# MKRZero_V5_0.net
KiCad netlist of a schematic drawn in EAGLE
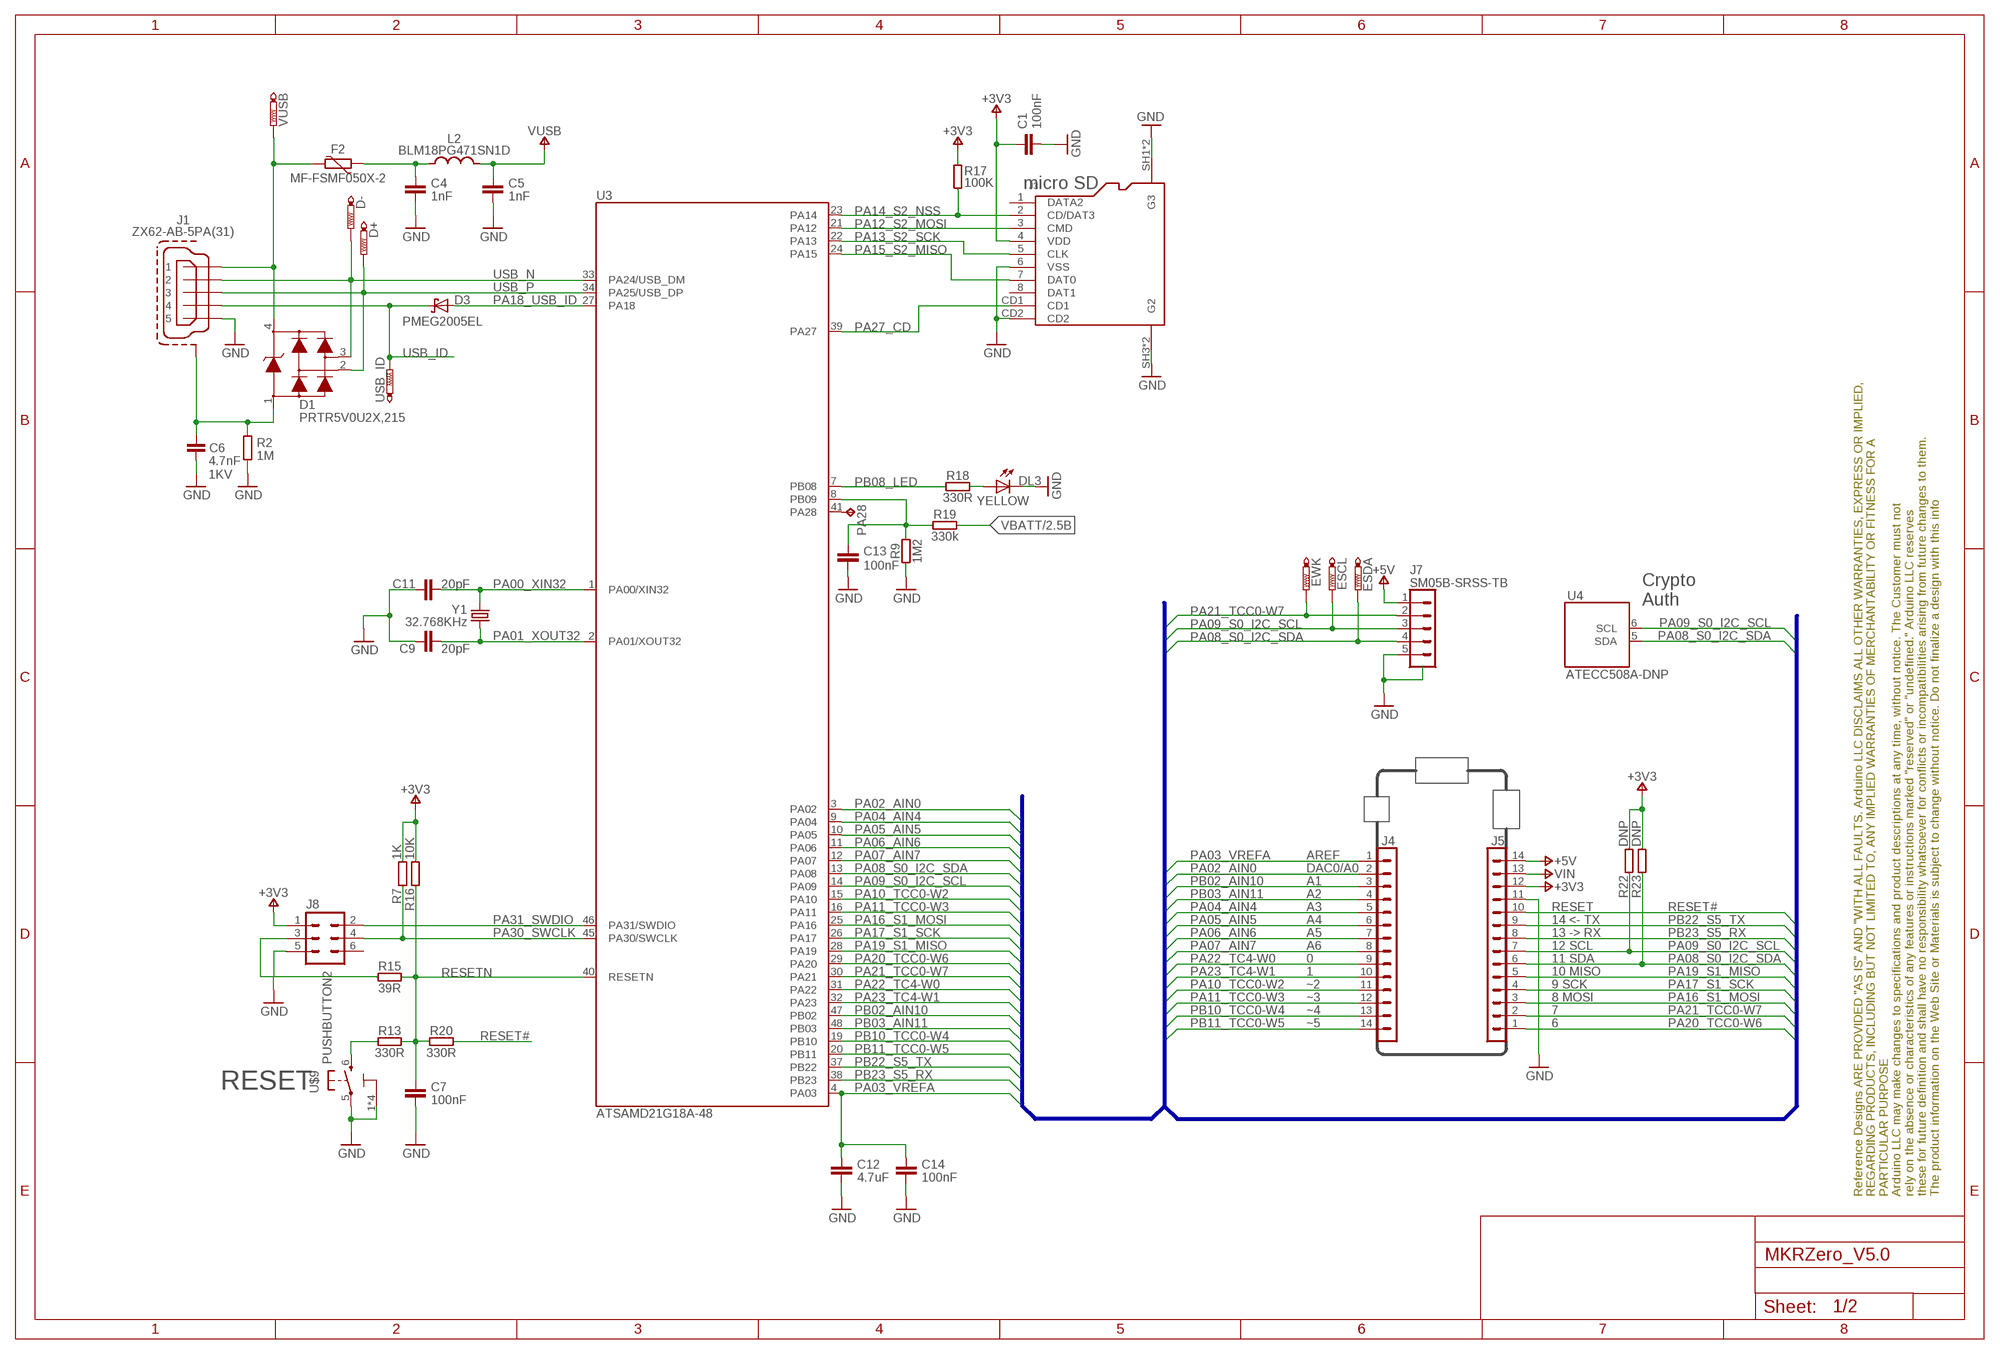
[diagram p0: schematic, sheet 1]
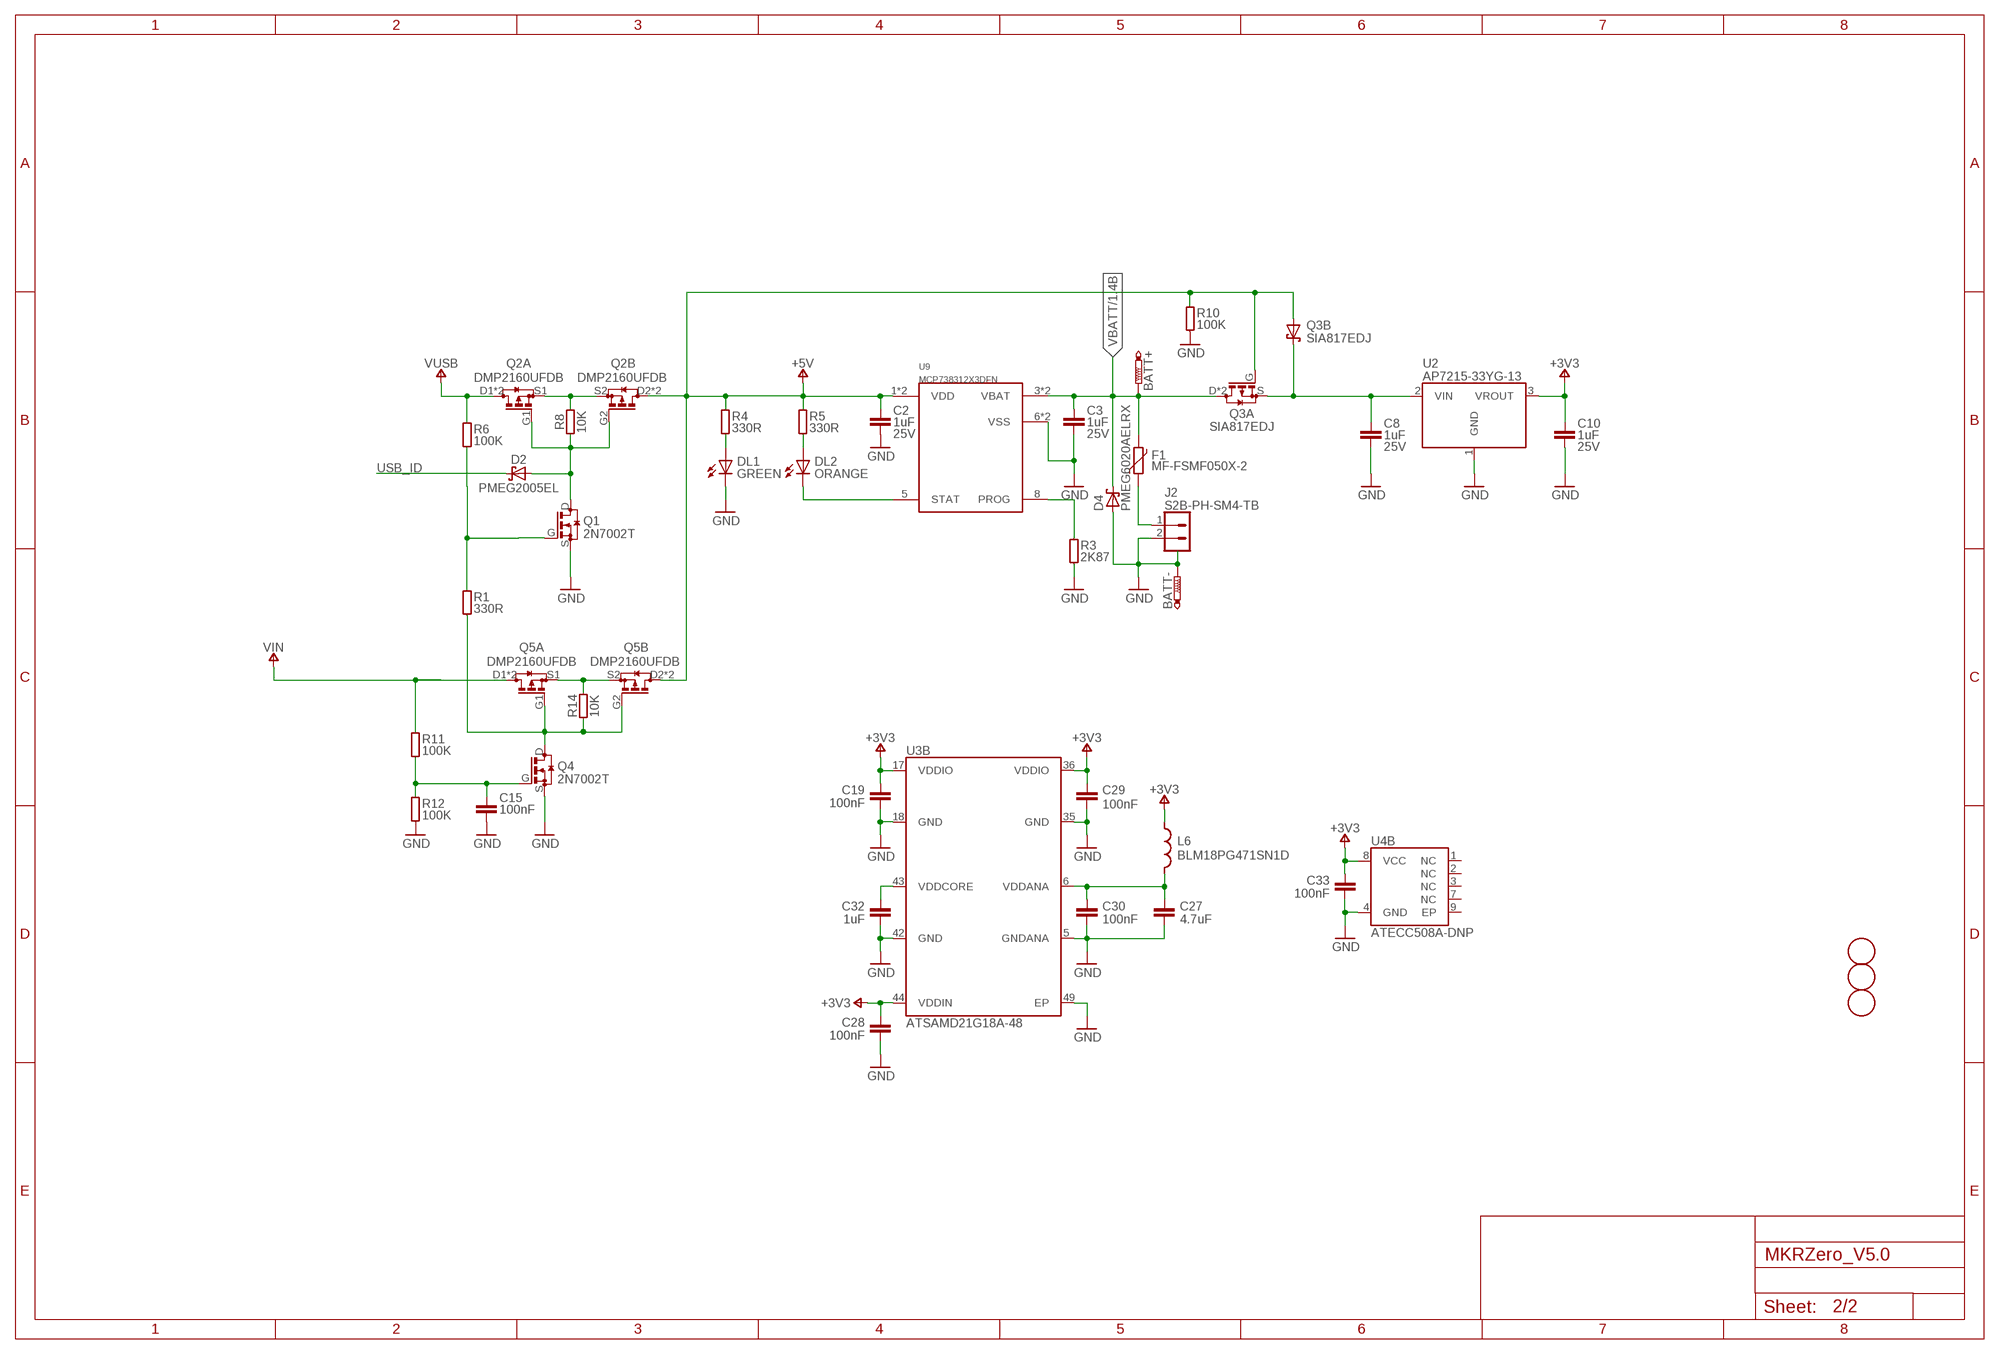
[diagram p1: schematic, sheet 2]

(export (version "E")
  (design (tool "Eeschema 10.0.6"))
  (components
    (comp (ref "BATT+")
      (value "PTR1B1,27")
      (footprint "eagle-import:B1,27")
      (libsource (lib "eagle-import") (part "PTR1B1,27"))
    )
    (comp (ref "BATT-")
      (value "PTR1B1,27")
      (footprint "eagle-import:B1,27")
      (libsource (lib "eagle-import") (part "PTR1B1,27"))
    )
    (comp (ref "C2")
      (value "1uF")
      (footprint "eagle-import:0402-1005X55N")
      (fields
        (field (name "MF") "Murata")
        (field (name "MPN") "GRM155R61E105KA12D ")
        (field (name "VOLTAGE") "25V")
      )
      (libsource (lib "eagle-import") (part "C-0402-1UF"))
    )
    (comp (ref "C3")
      (value "1uF")
      (footprint "eagle-import:0402-1005X55N")
      (fields
        (field (name "MF") "Murata")
        (field (name "MPN") "GRM155R61E105KA12D ")
        (field (name "VOLTAGE") "25V")
      )
      (libsource (lib "eagle-import") (part "C-0402-1UF"))
    )
    (comp (ref "C8")
      (value "1uF")
      (footprint "eagle-import:0402-1005X55N")
      (fields
        (field (name "MF") "Murata")
        (field (name "MPN") "GRM155R61E105KA12D ")
        (field (name "VOLTAGE") "25V")
      )
      (libsource (lib "eagle-import") (part "C-0402-1UF"))
    )
    (comp (ref "C10")
      (value "1uF")
      (footprint "eagle-import:0402-1005X55N")
      (fields
        (field (name "MF") "Murata")
        (field (name "MPN") "GRM155R61E105KA12D ")
        (field (name "VOLTAGE") "25V")
      )
      (libsource (lib "eagle-import") (part "C-0402-1UF"))
    )
    (comp (ref "C15")
      (value "100nF")
      (footprint "eagle-import:0402-1005X55N")
      (fields
        (field (name "MF") "Murata")
        (field (name "MPN") "GRM155R61E105KA12D ")
        (field (name "VOLTAGE") "25V")
      )
      (libsource (lib "eagle-import") (part "C-0402-1UF"))
    )
    (comp (ref "C19")
      (value "100nF")
      (footprint "eagle-import:0402-1005X55N")
      (fields (field (name "MF") "TDK") (field (name "MPN") "C1005X5R1H104K050BB "))
      (libsource (lib "eagle-import") (part "C-0402-100NF"))
    )
    (comp (ref "C27")
      (value "4.7uF")
      (footprint "eagle-import:0402-1005X55N")
      (fields (field (name "MF") "Murata") (field (name "MPN") "GRM155R60J475ME47D "))
      (libsource (lib "eagle-import") (part "C-0402-4.7UF"))
    )
    (comp (ref "C28")
      (value "100nF")
      (footprint "eagle-import:0402-1005X55N")
      (fields (field (name "MF") "TDK") (field (name "MPN") "C1005X5R1H104K050BB "))
      (libsource (lib "eagle-import") (part "C-0402-100NF"))
    )
    (comp (ref "C29")
      (value "100nF")
      (footprint "eagle-import:0402-1005X55N")
      (fields (field (name "MF") "TDK") (field (name "MPN") "C1005X5R1H104K050BB "))
      (libsource (lib "eagle-import") (part "C-0402-100NF"))
    )
    (comp (ref "C30")
      (value "100nF")
      (footprint "eagle-import:0402-1005X55N")
      (fields (field (name "MF") "TDK") (field (name "MPN") "C1005X5R1H104K050BB "))
      (libsource (lib "eagle-import") (part "C-0402-100NF"))
    )
    (comp (ref "C32")
      (value "1uF")
      (footprint "eagle-import:0402-1005X55N")
      (fields (field (name "MF") "Murata") (field (name "MPN") "GRM155R61E105KA12D "))
      (libsource (lib "eagle-import") (part "C-0402-1UF"))
    )
    (comp (ref "C33")
      (value "100nF")
      (footprint "eagle-import:0402-1005X55N")
      (fields (field (name "MF") "TDK") (field (name "MPN") "C1005X5R1H104K050BB "))
      (libsource (lib "eagle-import") (part "C-0402-100NF"))
    )
    (comp (ref "D2")
      (value "PMEG2005EL")
      (footprint "eagle-import:SODFL1008X40N-882D")
      (fields (field (name "MF") "NXP") (field (name "MPN") "PMEG2005EL,315 "))
      (libsource (lib "eagle-import") (part "PMEG2005EL"))
    )
    (comp (ref "D4")
      (value "PMEG6020AELRX")
      (footprint "eagle-import:SMA_DO123")
      (libsource (lib "eagle-import") (part "D_SCHOTTKYSO123"))
    )
    (comp (ref "DL1")
      (value "GREEN")
      (footprint "eagle-import:LEDC1608X80N-AK")
      (fields (field (name "MF") "Avago ") (field (name "MPN") "HSMG-C190 "))
      (libsource (lib "eagle-import") (part "LED-0603-GREEN"))
    )
    (comp (ref "DL2")
      (value "ORANGE")
      (footprint "eagle-import:LEDC1608X80N-AK")
      (fields (field (name "MF") "Avago ") (field (name "MPN") "HSMD-C190 "))
      (libsource (lib "eagle-import") (part "LED-0603-ORANGE"))
    )
    (comp (ref "F1")
      (value "MF-FSMF050X-2")
      (footprint "eagle-import:0603-F1608X100N")
      (fields (field (name "MF") "Bourns Inc ") (field (name "MPN") "MF-FSMF050X-2 "))
      (libsource (lib "eagle-import") (part "MF-FSMF050X-2"))
    )
    (comp (ref "FD1")
      (value "FIDUCIALMOUNT")
      (footprint "eagle-import:FIDUCIAL-MOUNT")
      (libsource (lib "eagle-import") (part "FIDUCIALMOUNT"))
    )
    (comp (ref "FD2")
      (value "FIDUCIALMOUNT")
      (footprint "eagle-import:FIDUCIAL-MOUNT")
      (libsource (lib "eagle-import") (part "FIDUCIALMOUNT"))
    )
    (comp (ref "FD3")
      (value "FIDUCIALMOUNT")
      (footprint "eagle-import:FIDUCIAL-MOUNT")
      (libsource (lib "eagle-import") (part "FIDUCIALMOUNT"))
    )
    (comp (ref "J2")
      (value "S2B-PH-SM4-TB")
      (footprint "eagle-import:JST-S2B-PH-SM4-TB")
      (fields (field (name "MF") "JST ") (field (name "MPN") "S2B-PH-SM4-TB(LF)(SN) "))
      (libsource (lib "eagle-import") (part "S2B-PH-SM4-TB"))
    )
    (comp (ref "L6")
      (value "BLM18PG471SN1D")
      (footprint "eagle-import:0603-1608X90N")
      (libsource (lib "eagle-import") (part "BLM18PG471SN1D"))
    )
    (comp (ref "Q1")
      (value "2N7002T")
      (footprint "eagle-import:SOTFL50P160X78-3")
      (fields (field (name "MF") "Fairchild"))
      (libsource (lib "eagle-import") (part "2N7002T"))
    )
    (comp (ref "Q2")
      (value "DMP2160UFDB")
      (footprint "eagle-import:SON65P200X200X60-8N-DM")
      (fields (field (name "MF") "Diodes Inc ") (field (name "MPN") "DMP2160UFDB-7 "))
      (libsource (lib "eagle-import") (part "DMP2160UFDB"))
    )
    (comp (ref "Q3")
      (value "SIA817EDJ")
      (footprint "eagle-import:SON65P205X205X75-8N-MWSD")
      (fields (field (name "MF") "Vishay ") (field (name "MPN") "SIA817EDJ-T1-GE3 "))
      (libsource (lib "eagle-import") (part "SIA817EDJ"))
    )
    (comp (ref "Q4")
      (value "2N7002T")
      (footprint "eagle-import:SOTFL50P160X78-3")
      (fields (field (name "MF") "Fairchild"))
      (libsource (lib "eagle-import") (part "2N7002T"))
    )
    (comp (ref "Q5")
      (value "DMP2160UFDB")
      (footprint "eagle-import:SON65P200X200X60-8N-DM")
      (fields (field (name "MF") "Diodes Inc ") (field (name "MPN") "DMP2160UFDB-7 "))
      (libsource (lib "eagle-import") (part "DMP2160UFDB"))
    )
    (comp (ref "R1")
      (value "330R")
      (footprint "eagle-import:0402-1005X55N")
      (fields (field (name "MF") "Yageo ") (field (name "MPN") "RC0402FR-07330RL "))
      (libsource (lib "eagle-import") (part "R-0402-330R"))
    )
    (comp (ref "R3")
      (value "2K87")
      (footprint "eagle-import:0402-1005X55N")
      (fields (field (name "MF") "Yageo") (field (name "MPN") "RC0402FR-072K87L"))
      (libsource (lib "eagle-import") (part "R-0402-2K87"))
    )
    (comp (ref "R4")
      (value "330R")
      (footprint "eagle-import:0402-1005X55N")
      (fields (field (name "MF") "Yageo ") (field (name "MPN") "RC0402FR-07330RL "))
      (libsource (lib "eagle-import") (part "R-0402-330R"))
    )
    (comp (ref "R5")
      (value "330R")
      (footprint "eagle-import:0402-1005X55N")
      (fields (field (name "MF") "Yageo ") (field (name "MPN") "RC0402FR-07330RL "))
      (libsource (lib "eagle-import") (part "R-0402-330R"))
    )
    (comp (ref "R6")
      (value "100K")
      (footprint "eagle-import:0402-1005X55N")
      (fields (field (name "MF") "Yageo ") (field (name "MPN") "RC0402FR-07100KL "))
      (libsource (lib "eagle-import") (part "R-0402-100K"))
    )
    (comp (ref "R8")
      (value "10K")
      (footprint "eagle-import:0402-1005X55N")
      (fields (field (name "MF") "Yageo") (field (name "MPN") "RC0402FR-0710KL"))
      (libsource (lib "eagle-import") (part "R-0402-10K"))
    )
    (comp (ref "R10")
      (value "100K")
      (footprint "eagle-import:0402-1005X55N")
      (fields (field (name "MF") "Yageo ") (field (name "MPN") "RC0402FR-07100KL "))
      (libsource (lib "eagle-import") (part "R-0402-100K"))
    )
    (comp (ref "R11")
      (value "100K")
      (footprint "eagle-import:0402-1005X55N")
      (fields (field (name "MF") "Yageo ") (field (name "MPN") "RC0402FR-07100KL "))
      (libsource (lib "eagle-import") (part "R-0402-100K"))
    )
    (comp (ref "R12")
      (value "100K")
      (footprint "eagle-import:0402-1005X55N")
      (fields (field (name "MF") "Yageo ") (field (name "MPN") "RC0402FR-07100KL "))
      (libsource (lib "eagle-import") (part "R-0402-100K"))
    )
    (comp (ref "R14")
      (value "10K")
      (footprint "eagle-import:0402-1005X55N")
      (fields (field (name "MF") "Yageo") (field (name "MPN") "RC0402FR-0710KL"))
      (libsource (lib "eagle-import") (part "R-0402-10K"))
    )
    (comp (ref "U2")
      (value "AP7215-33YG-13")
      (footprint "eagle-import:SOT150P400X160-3N")
      (fields (field (name "MF") "Diodes Inc ") (field (name "MPN") "AP7215-33YG-13 "))
      (libsource (lib "eagle-import") (part "AP7215-33YG-13"))
    )
    (comp (ref "U3")
      (value "ATSAMD21G18A-48")
      (footprint "eagle-import:QFN50P700X700X90-49XN-EPSQ515")
      (fields (field (name "MF") "Atmel") (field (name "MPN") "ATSAMD21E18A-MU "))
      (libsource (lib "eagle-import") (part "ATSAMD21G18A-48"))
    )
    (comp (ref "U4")
      (value "ATECC508A-DNP")
      (footprint "eagle-import:SON50P300X200X60-9N-EP160X140")
      (fields (field (name "MF") "Atmel") (field (name "MPN") "ATECC508A-MAHDA-T "))
      (libsource (lib "eagle-import") (part "ATECC508A-MAHDA-T"))
    )
    (comp (ref "U9")
      (value "MCP738312X3DFN")
      (footprint "eagle-import:2X3DFN")
      (libsource (lib "eagle-import") (part "MCP738312X3DFN"))
    )
    (comp (ref "C1")
      (value "100nF")
      (footprint "eagle-import:0402-1005X55N")
      (fields (field (name "MF") "TDK") (field (name "MPN") "C1005X5R1H104K050BB "))
      (libsource (lib "eagle-import") (part "C-0402-100NF"))
    )
    (comp (ref "C4")
      (value "1nF")
      (footprint "eagle-import:0402-1005X55N")
      (fields (field (name "MF") "Murata ") (field (name "MPN") "GRM155R71H103KA88J "))
      (libsource (lib "eagle-import") (part "C-0402-10NF"))
    )
    (comp (ref "C5")
      (value "1nF")
      (footprint "eagle-import:0402-1005X55N")
      (fields (field (name "MF") "TDK") (field (name "MPN") "C1005X5R1H104K050BB "))
      (libsource (lib "eagle-import") (part "C-0402-100NF"))
    )
    (comp (ref "C6")
      (value "4.7nF")
      (footprint "eagle-import:C0805")
      (fields (field (name "VOLTAGE") "1KV"))
      (libsource (lib "eagle-import") (part "CAPACITORS-0805"))
    )
    (comp (ref "C7")
      (value "100nF")
      (footprint "eagle-import:0402-1005X55N")
      (fields (field (name "MF") "TDK") (field (name "MPN") "C1005X5R1H104K050BB "))
      (libsource (lib "eagle-import") (part "C-0402-100NF"))
    )
    (comp (ref "C9")
      (value "20pF")
      (footprint "eagle-import:0402-1005X55N")
      (fields (field (name "MF") "Kemet") (field (name "MPN") "CBR04C200J5GAC "))
      (libsource (lib "eagle-import") (part "C-0402-20PF"))
    )
    (comp (ref "C11")
      (value "20pF")
      (footprint "eagle-import:0402-1005X55N")
      (fields (field (name "MF") "Kemet") (field (name "MPN") "CBR04C200J5GAC "))
      (libsource (lib "eagle-import") (part "C-0402-20PF"))
    )
    (comp (ref "C12")
      (value "4.7uF")
      (footprint "eagle-import:0402-1005X55N")
      (fields (field (name "MF") "Murata") (field (name "MPN") "GRM155R60J475ME47D "))
      (libsource (lib "eagle-import") (part "C-0402-4.7UF"))
    )
    (comp (ref "C13")
      (value "100nF")
      (footprint "eagle-import:0402-1005X55N")
      (fields (field (name "MF") "TDK") (field (name "MPN") "C1005X5R1H104K050BB "))
      (libsource (lib "eagle-import") (part "C-0402-100NF"))
    )
    (comp (ref "C14")
      (value "100nF")
      (footprint "eagle-import:0402-1005X55N")
      (fields (field (name "MF") "TDK") (field (name "MPN") "C1005X5R1H104K050BB "))
      (libsource (lib "eagle-import") (part "C-0402-100NF"))
    )
    (comp (ref "D+")
      (value "PTR1B1,27")
      (footprint "eagle-import:B1,27")
      (libsource (lib "eagle-import") (part "PTR1B1,27"))
    )
    (comp (ref "D-")
      (value "PTR1B1,27")
      (footprint "eagle-import:B1,27")
      (libsource (lib "eagle-import") (part "PTR1B1,27"))
    )
    (comp (ref "D1")
      (value "PRTR5V0U2X,215")
      (footprint "eagle-import:SOT190P230X110-4N")
      (fields (field (name "MF") "NXP") (field (name "MPN") "PRTR5V0U2X,215 "))
      (libsource (lib "eagle-import") (part "PRTR5V0U2X,215"))
    )
    (comp (ref "D3")
      (value "PMEG2005EL")
      (footprint "eagle-import:SODFL1008X40N-882D")
      (fields (field (name "MF") "NXP") (field (name "MPN") "PMEG2005EL,315 "))
      (libsource (lib "eagle-import") (part "PMEG2005EL"))
    )
    (comp (ref "DL3")
      (value "YELLOW")
      (footprint "eagle-import:LEDC1608X80N-AK")
      (fields (field (name "MF") "Avago ") (field (name "MPN") "HSMG-C190 "))
      (libsource (lib "eagle-import") (part "LED-0603-GREEN"))
    )
    (comp (ref "ESCL")
      (value "PTR1B1,27")
      (footprint "eagle-import:B1,27")
      (libsource (lib "eagle-import") (part "PTR1B1,27"))
    )
    (comp (ref "ESDA")
      (value "PTR1B1,27")
      (footprint "eagle-import:B1,27")
      (libsource (lib "eagle-import") (part "PTR1B1,27"))
    )
    (comp (ref "EWK")
      (value "PTR1B1,27")
      (footprint "eagle-import:B1,27")
      (libsource (lib "eagle-import") (part "PTR1B1,27"))
    )
    (comp (ref "F2")
      (value "MF-FSMF050X-2")
      (footprint "eagle-import:0603-F1608X100N")
      (fields (field (name "MF") "Bourns Inc ") (field (name "MPN") "MF-FSMF050X-2 "))
      (libsource (lib "eagle-import") (part "MF-FSMF050X-2"))
    )
    (comp (ref "FRAME1")
      (value "Page 1")
      (footprint "eagle-import:FRAME")
      (libsource (lib "eagle-import") (part "A3L-LOC"))
    )
    (comp (ref "J1")
      (value "ZX62-AB-5PA(31)")
      (footprint "eagle-import:USBMICRO-ZX62-AB-5PA")
      (libsource (lib "eagle-import") (part "ZX62AB-5PA(11)"))
    )
    (comp (ref "J3")
      (value "AMPHENOL_114-00841-68")
      (footprint "eagle-import:AMPHENOL_114-00841-68")
      (libsource (lib "eagle-import") (part "AMPHENOL_114-00841-68"))
    )
    (comp (ref "J4")
      (value "DNP")
      (footprint "eagle-import:STRIP-14-MODULI-A11")
      (libsource (lib "eagle-import") (part "STRIP-14"))
    )
    (comp (ref "J5")
      (value "DNP")
      (footprint "eagle-import:STRIP-14-MODULI-A11")
      (libsource (lib "eagle-import") (part "STRIP-14"))
    )
    (comp (ref "J7")
      (value "SM05B-SRSS-TB")
      (footprint "eagle-import:SM05B-SRSS-TB")
      (fields (field (name "MF") "JST"))
      (libsource (lib "eagle-import") (part "SM05B-SRSS-TB"))
    )
    (comp (ref "J8")
      (value "2X3_SMD_MALE")
      (footprint "eagle-import:2X3_SMT")
      (libsource (lib "eagle-import") (part "2X3_SMD_MALE"))
    )
    (comp (ref "L2")
      (value "BLM18PG471SN1D")
      (footprint "eagle-import:0603-1608X90N")
      (libsource (lib "eagle-import") (part "BLM18PG471SN1D"))
    )
    (comp (ref "PA28")
      (value "TPB2,54")
      (footprint "eagle-import:B2,54")
      (libsource (lib "eagle-import") (part "TPB2,54"))
    )
    (comp (ref "R2")
      (value "1M")
      (footprint "eagle-import:0402-1005X55N")
      (fields (field (name "MF") "Yageo") (field (name "MPN") "RC0402FR-071ML"))
      (libsource (lib "eagle-import") (part "R-0402-1M"))
    )
    (comp (ref "R7")
      (value "1K")
      (footprint "eagle-import:0402-1005X55N")
      (fields (field (name "MF") "Yageo") (field (name "MPN") "RC0402FR-071KL"))
      (libsource (lib "eagle-import") (part "R-0402-1K"))
    )
    (comp (ref "R9")
      (value "1M2")
      (footprint "eagle-import:0402-1005X55N")
      (fields (field (name "MF") "Yageo ") (field (name "MPN") "RC0402FR-07330RL "))
      (libsource (lib "eagle-import") (part "R-0402-330R"))
    )
    (comp (ref "R13")
      (value "330R")
      (footprint "eagle-import:0402-1005X55N")
      (fields (field (name "MF") "Yageo ") (field (name "MPN") "RC0402FR-07330RL "))
      (libsource (lib "eagle-import") (part "R-0402-330R"))
    )
    (comp (ref "R15")
      (value "39R")
      (footprint "eagle-import:0402-1005X55N")
      (fields (field (name "MF") "Yageo ") (field (name "MPN") "RC0402FR-0739RL "))
      (libsource (lib "eagle-import") (part "R-0402-39R"))
    )
    (comp (ref "R16")
      (value "10K")
      (footprint "eagle-import:0402-1005X55N")
      (fields (field (name "MF") "Yageo") (field (name "MPN") "RC0402FR-0710KL"))
      (libsource (lib "eagle-import") (part "R-0402-10K"))
    )
    (comp (ref "R17")
      (value "100K")
      (footprint "eagle-import:0402-1005X55N")
      (fields (field (name "MF") "Yageo ") (field (name "MPN") "RC0402FR-07100KL "))
      (libsource (lib "eagle-import") (part "R-0402-100K"))
    )
    (comp (ref "R18")
      (value "330R")
      (footprint "eagle-import:0402-1005X55N")
      (fields (field (name "MF") "Yageo ") (field (name "MPN") "RC0402FR-07330RL "))
      (libsource (lib "eagle-import") (part "R-0402-330R"))
    )
    (comp (ref "R19")
      (value "330k")
      (footprint "eagle-import:0402-1005X55N")
      (fields (field (name "MF") "Yageo ") (field (name "MPN") "RC0402FR-07330RL "))
      (libsource (lib "eagle-import") (part "R-0402-330R"))
    )
    (comp (ref "R20")
      (value "330R")
      (footprint "eagle-import:0402-1005X55N")
      (fields (field (name "MF") "Yageo ") (field (name "MPN") "RC0402FR-07330RL "))
      (libsource (lib "eagle-import") (part "R-0402-330R"))
    )
    (comp (ref "R22")
      (value "DNP")
      (footprint "eagle-import:0402-1005X55N")
      (fields (field (name "MF") "Yageo ") (field (name "MPN") "RC0402FR-074K7L "))
      (libsource (lib "eagle-import") (part "R-0402-4K7"))
    )
    (comp (ref "R23")
      (value "DNP")
      (footprint "eagle-import:0402-1005X55N")
      (fields (field (name "MF") "Yageo ") (field (name "MPN") "RC0402FR-074K7L "))
      (libsource (lib "eagle-import") (part "R-0402-4K7"))
    )
    (comp (ref "U$9")
      (value "PUSHBUTTON2")
      (footprint "eagle-import:C&K_PTS820_NOPEGS")
      (libsource (lib "eagle-import") (part "PUSHBUTTON2"))
    )
    (comp (ref "USB_ID")
      (value "PTR1B1,27")
      (footprint "eagle-import:B1,27")
      (libsource (lib "eagle-import") (part "PTR1B1,27"))
    )
    (comp (ref "VUSB")
      (value "PTR1B1,27")
      (footprint "eagle-import:B1,27")
      (libsource (lib "eagle-import") (part "PTR1B1,27"))
    )
    (comp (ref "Y1")
      (value "32.768KHz")
      (footprint "eagle-import:QUARZO-ABS07")
      (fields (field (name "MF") "Abracon ") (field (name "MPN") "ABS07-32.768KHZ-T "))
      (libsource (lib "eagle-import") (part "ABS07-32.768KHZ-T"))
    )
  )
  (nets
    (net (code "1") (name "+3V3") (class "Default")
      (node (ref "C1") (pin "1") (pinfunction "1_1") (pintype "passive"))
      (node (ref "C10") (pin "1") (pinfunction "1_1") (pintype "passive"))
      (node (ref "C19") (pin "1") (pinfunction "1_1") (pintype "passive"))
      (node (ref "C28") (pin "1") (pinfunction "1_1") (pintype "passive"))
      (node (ref "C29") (pin "1") (pinfunction "1_1") (pintype "passive"))
      (node (ref "C33") (pin "1") (pinfunction "1_1") (pintype "passive"))
      (node (ref "J3") (pin "4") (pinfunction "VDD_4") (pintype "power_in"))
      (node (ref "J5") (pin "12") (pinfunction "12_12") (pintype "passive"))
      (node (ref "J8") (pin "1") (pinfunction "1_1") (pintype "passive"))
      (node (ref "L6") (pin "1") (pinfunction "1_1") (pintype "passive"))
      (node (ref "R16") (pin "2") (pinfunction "2_2") (pintype "passive"))
      (node (ref "R17") (pin "2") (pinfunction "2_2") (pintype "passive"))
      (node (ref "R22") (pin "2") (pinfunction "2_2") (pintype "passive"))
      (node (ref "R23") (pin "2") (pinfunction "2_2") (pintype "passive"))
      (node (ref "R7") (pin "2") (pinfunction "2_2") (pintype "passive"))
      (node (ref "U2") (pin "3") (pinfunction "VROUT_3") (pintype "power_in"))
      (node (ref "U3") (pin "17") (pinfunction "VDDIO_17") (pintype "power_in"))
      (node (ref "U3") (pin "36") (pinfunction "VDDIO_36") (pintype "power_in"))
      (node (ref "U3") (pin "44") (pinfunction "VDDIN_44") (pintype "power_in"))
      (node (ref "U4") (pin "8") (pinfunction "VCC_8") (pintype "power_in"))
    )
    (net (code "2") (name "+5V") (class "Default")
      (node (ref "C2") (pin "1") (pinfunction "1_1") (pintype "passive"))
      (node (ref "J5") (pin "14") (pinfunction "14_14") (pintype "passive"))
      (node (ref "J7") (pin "1") (pinfunction "1_1") (pintype "passive"))
      (node (ref "Q2") (pin "D2") (pinfunction "D_D2") (pintype "passive"))
      (node (ref "Q2") (pin "D2'") (pinfunction "D_D2'") (pintype "passive"))
      (node (ref "Q3") (pin "A") (pinfunction "A_A") (pintype "passive"))
      (node (ref "Q3") (pin "G") (pinfunction "G_G") (pintype "passive"))
      (node (ref "Q5") (pin "D2") (pinfunction "D_D2") (pintype "passive"))
      (node (ref "Q5") (pin "D2'") (pinfunction "D_D2'") (pintype "passive"))
      (node (ref "R10") (pin "2") (pinfunction "2_2") (pintype "passive"))
      (node (ref "R4") (pin "2") (pinfunction "2_2") (pintype "passive"))
      (node (ref "R5") (pin "2") (pinfunction "2_2") (pintype "passive"))
      (node (ref "U9") (pin "1") (pinfunction "VDD_1") (pintype "bidirectional"))
      (node (ref "U9") (pin "2") (pinfunction "VDD_2") (pintype "bidirectional"))
    )
    (net (code "3") (name "GND") (class "Default")
      (node (ref "BATT-") (pin "PP") (pinfunction "TP_PP") (pintype "input"))
      (node (ref "C1") (pin "2") (pinfunction "2_2") (pintype "passive"))
      (node (ref "C10") (pin "2") (pinfunction "2_2") (pintype "passive"))
      (node (ref "C11") (pin "1") (pinfunction "1_1") (pintype "passive"))
      (node (ref "C12") (pin "2") (pinfunction "2_2") (pintype "passive"))
      (node (ref "C13") (pin "2") (pinfunction "2_2") (pintype "passive"))
      (node (ref "C14") (pin "2") (pinfunction "2_2") (pintype "passive"))
      (node (ref "C15") (pin "2") (pinfunction "2_2") (pintype "passive"))
      (node (ref "C19") (pin "2") (pinfunction "2_2") (pintype "passive"))
      (node (ref "C2") (pin "2") (pinfunction "2_2") (pintype "passive"))
      (node (ref "C27") (pin "2") (pinfunction "2_2") (pintype "passive"))
      (node (ref "C28") (pin "2") (pinfunction "2_2") (pintype "passive"))
      (node (ref "C29") (pin "2") (pinfunction "2_2") (pintype "passive"))
      (node (ref "C3") (pin "2") (pinfunction "2_2") (pintype "passive"))
      (node (ref "C30") (pin "2") (pinfunction "2_2") (pintype "passive"))
      (node (ref "C32") (pin "2") (pinfunction "2_2") (pintype "passive"))
      (node (ref "C33") (pin "2") (pinfunction "2_2") (pintype "passive"))
      (node (ref "C4") (pin "2") (pinfunction "2_2") (pintype "passive"))
      (node (ref "C5") (pin "2") (pinfunction "2_2") (pintype "passive"))
      (node (ref "C6") (pin "2") (pinfunction "2_2") (pintype "passive"))
      (node (ref "C7") (pin "2") (pinfunction "2_2") (pintype "passive"))
      (node (ref "C8") (pin "2") (pinfunction "2_2") (pintype "passive"))
      (node (ref "C9") (pin "1") (pinfunction "1_1") (pintype "passive"))
      (node (ref "D4") (pin "A") (pinfunction "A_A") (pintype "passive"))
      (node (ref "DL1") (pin "C") (pinfunction "C_C") (pintype "passive"))
      (node (ref "DL3") (pin "C") (pinfunction "C_C") (pintype "passive"))
      (node (ref "J1") (pin "5") (pinfunction "5_5") (pintype "passive"))
      (node (ref "J2") (pin "2") (pinfunction "2_2") (pintype "passive"))
      (node (ref "J2") (pin "3") (pinfunction "SH_3") (pintype "passive"))
      (node (ref "J2") (pin "4") (pinfunction "SH_4") (pintype "passive"))
      (node (ref "J3") (pin "6") (pinfunction "VSS_6") (pintype "power_in"))
      (node (ref "J3") (pin "CD2") (pinfunction "CD2_CD2") (pintype "bidirectional"))
      (node (ref "J3") (pin "SH1") (pinfunction "G3_SH1") (pintype "bidirectional"))
      (node (ref "J3") (pin "SH2") (pinfunction "G3_SH2") (pintype "bidirectional"))
      (node (ref "J3") (pin "SH3") (pinfunction "G2_SH3") (pintype "bidirectional"))
      (node (ref "J3") (pin "SH4") (pinfunction "G2_SH4") (pintype "bidirectional"))
      (node (ref "J5") (pin "11") (pinfunction "11_11") (pintype "passive"))
      (node (ref "J7") (pin "5") (pinfunction "5_5") (pintype "passive"))
      (node (ref "J7") (pin "SH1") (pinfunction "SH_SH1") (pintype "passive"))
      (node (ref "J7") (pin "SH2") (pinfunction "SH_SH2") (pintype "passive"))
      (node (ref "J8") (pin "5") (pinfunction "5_5") (pintype "passive"))
      (node (ref "Q1") (pin "S") (pinfunction "S_S") (pintype "passive"))
      (node (ref "Q4") (pin "S") (pinfunction "S_S") (pintype "passive"))
      (node (ref "R10") (pin "1") (pinfunction "1_1") (pintype "passive"))
      (node (ref "R12") (pin "1") (pinfunction "1_1") (pintype "passive"))
      (node (ref "R2") (pin "1") (pinfunction "1_1") (pintype "passive"))
      (node (ref "R3") (pin "1") (pinfunction "1_1") (pintype "passive"))
      (node (ref "R9") (pin "1") (pinfunction "1_1") (pintype "passive"))
      (node (ref "U$9") (pin "1") (pinfunction "3_1") (pintype "power_in"))
      (node (ref "U$9") (pin "2") (pinfunction "3_2") (pintype "power_in"))
      (node (ref "U$9") (pin "3") (pinfunction "3_3") (pintype "power_in"))
      (node (ref "U$9") (pin "4") (pinfunction "3_4") (pintype "power_in"))
      (node (ref "U$9") (pin "5") (pinfunction "1_5") (pintype "passive"))
      (node (ref "U2") (pin "1") (pinfunction "GND_1") (pintype "power_in"))
      (node (ref "U3") (pin "18") (pinfunction "GND_18") (pintype "power_in"))
      (node (ref "U3") (pin "35") (pinfunction "GND_35") (pintype "power_in"))
      (node (ref "U3") (pin "42") (pinfunction "GND_42") (pintype "power_in"))
      (node (ref "U3") (pin "49") (pinfunction "EP_49") (pintype "passive"))
      (node (ref "U3") (pin "5") (pinfunction "GNDANA_5") (pintype "power_in"))
      (node (ref "U4") (pin "4") (pinfunction "GND_4") (pintype "power_in"))
      (node (ref "U9") (pin "6") (pinfunction "VSS_6") (pintype "bidirectional"))
      (node (ref "U9") (pin "PAD") (pinfunction "VSS_PAD") (pintype "bidirectional"))
    )
    (net (code "4") (name "Net-(C4-Pad1)") (class "Default")
      (node (ref "C4") (pin "1") (pinfunction "1_1") (pintype "passive"))
      (node (ref "F2") (pin "1") (pinfunction "1_1") (pintype "passive"))
      (node (ref "L2") (pin "1") (pinfunction "1_1") (pintype "passive"))
    )
    (net (code "5") (name "Net-(C6-Pad1)") (class "Default")
      (node (ref "C6") (pin "1") (pinfunction "1_1") (pintype "passive"))
      (node (ref "D1") (pin "1") (pinfunction "1_1") (pintype "passive"))
      (node (ref "J1") (pin "10") (pinfunction "SH_10") (pintype "passive"))
      (node (ref "J1") (pin "11") (pinfunction "SH_11") (pintype "passive"))
      (node (ref "J1") (pin "6") (pinfunction "SH_6") (pintype "passive"))
      (node (ref "J1") (pin "7") (pinfunction "SH_7") (pintype "passive"))
      (node (ref "J1") (pin "8") (pinfunction "SH_8") (pintype "passive"))
      (node (ref "J1") (pin "9") (pinfunction "SH_9") (pintype "passive"))
      (node (ref "R2") (pin "2") (pinfunction "2_2") (pintype "passive"))
    )
    (net (code "6") (name "Net-(C15-Pad1)") (class "Default")
      (node (ref "C15") (pin "1") (pinfunction "1_1") (pintype "passive"))
      (node (ref "Q4") (pin "G") (pinfunction "G_G") (pintype "passive"))
      (node (ref "R11") (pin "1") (pinfunction "1_1") (pintype "passive"))
      (node (ref "R12") (pin "2") (pinfunction "2_2") (pintype "passive"))
    )
    (net (code "7") (name "Net-(DL1-PadA)") (class "Default")
      (node (ref "DL1") (pin "A") (pinfunction "A_A") (pintype "passive"))
      (node (ref "R4") (pin "1") (pinfunction "1_1") (pintype "passive"))
    )
    (net (code "8") (name "Net-(DL2-PadA)") (class "Default")
      (node (ref "DL2") (pin "A") (pinfunction "A_A") (pintype "passive"))
      (node (ref "R5") (pin "1") (pinfunction "1_1") (pintype "passive"))
    )
    (net (code "9") (name "Net-(DL3-PadA)") (class "Default")
      (node (ref "DL3") (pin "A") (pinfunction "A_A") (pintype "passive"))
      (node (ref "R18") (pin "2") (pinfunction "2_2") (pintype "passive"))
    )
    (net (code "10") (name "Net-(F1-Pad1)") (class "Default")
      (node (ref "F1") (pin "1") (pinfunction "1_1") (pintype "passive"))
      (node (ref "J2") (pin "1") (pinfunction "1_1") (pintype "passive"))
    )
    (net (code "11") (name "Net-(J8-Pad3)") (class "Default")
      (node (ref "J8") (pin "3") (pinfunction "3_3") (pintype "passive"))
      (node (ref "R15") (pin "1") (pinfunction "1_1") (pintype "passive"))
    )
    (net (code "12") (name "Net-(PA28-TP)") (class "Default")
      (node (ref "PA28") (pin "PP") (pinfunction "TP_PP") (pintype "input"))
      (node (ref "U3") (pin "41") (pinfunction "PA28_41") (pintype "bidirectional"))
    )
    (net (code "13") (name "Net-(Q1-PadG)") (class "Default")
      (node (ref "Q1") (pin "G") (pinfunction "G_G") (pintype "passive"))
      (node (ref "R1") (pin "2") (pinfunction "2_2") (pintype "passive"))
      (node (ref "R6") (pin "1") (pinfunction "1_1") (pintype "passive"))
    )
    (net (code "14") (name "Net-(Q2A-G)") (class "Default")
      (node (ref "D2") (pin "A") (pinfunction "A_A") (pintype "passive"))
      (node (ref "Q1") (pin "D") (pinfunction "D_D") (pintype "passive"))
      (node (ref "Q2") (pin "G1") (pinfunction "G_G1") (pintype "passive"))
      (node (ref "Q2") (pin "G2") (pinfunction "G_G2") (pintype "passive"))
      (node (ref "R8") (pin "1") (pinfunction "1_1") (pintype "passive"))
    )
    (net (code "15") (name "Net-(Q2A-S)") (class "Default")
      (node (ref "Q2") (pin "S1") (pinfunction "S_S1") (pintype "passive"))
      (node (ref "Q2") (pin "S2") (pinfunction "S_S2") (pintype "passive"))
      (node (ref "R8") (pin "2") (pinfunction "2_2") (pintype "passive"))
    )
    (net (code "16") (name "Net-(Q5A-G)") (class "Default")
      (node (ref "Q4") (pin "D") (pinfunction "D_D") (pintype "passive"))
      (node (ref "Q5") (pin "G1") (pinfunction "G_G1") (pintype "passive"))
      (node (ref "Q5") (pin "G2") (pinfunction "G_G2") (pintype "passive"))
      (node (ref "R1") (pin "1") (pinfunction "1_1") (pintype "passive"))
      (node (ref "R14") (pin "1") (pinfunction "1_1") (pintype "passive"))
    )
    (net (code "17") (name "Net-(Q5A-S)") (class "Default")
      (node (ref "Q5") (pin "S1") (pinfunction "S_S1") (pintype "passive"))
      (node (ref "Q5") (pin "S2") (pinfunction "S_S2") (pintype "passive"))
      (node (ref "R14") (pin "2") (pinfunction "2_2") (pintype "passive"))
    )
    (net (code "18") (name "Net-(U$9-2)") (class "Default")
      (node (ref "R13") (pin "1") (pinfunction "1_1") (pintype "passive"))
      (node (ref "U$9") (pin "6") (pinfunction "2_6") (pintype "passive"))
    )
    (net (code "19") (name "Net-(U2-VIN)") (class "Default")
      (node (ref "C8") (pin "1") (pinfunction "1_1") (pintype "passive"))
      (node (ref "Q3") (pin "K") (pinfunction "C_K") (pintype "passive"))
      (node (ref "Q3") (pin "K2") (pinfunction "C_K2") (pintype "passive"))
      (node (ref "Q3") (pin "S") (pinfunction "S_S") (pintype "passive"))
      (node (ref "U2") (pin "2") (pinfunction "VIN_2") (pintype "power_in"))
    )
    (net (code "20") (name "Net-(U3A-PB09)") (class "Default")
      (node (ref "C13") (pin "1") (pinfunction "1_1") (pintype "passive"))
      (node (ref "R19") (pin "1") (pinfunction "1_1") (pintype "passive"))
      (node (ref "R9") (pin "2") (pinfunction "2_2") (pintype "passive"))
      (node (ref "U3") (pin "8") (pinfunction "PB09_8") (pintype "bidirectional"))
    )
    (net (code "21") (name "Net-(U3B-VDDANA)") (class "Default")
      (node (ref "C27") (pin "1") (pinfunction "1_1") (pintype "passive"))
      (node (ref "C30") (pin "1") (pinfunction "1_1") (pintype "passive"))
      (node (ref "L6") (pin "2") (pinfunction "2_2") (pintype "passive"))
      (node (ref "U3") (pin "6") (pinfunction "VDDANA_6") (pintype "power_in"))
    )
    (net (code "22") (name "Net-(U3B-VDDCORE)") (class "Default")
      (node (ref "C32") (pin "1") (pinfunction "1_1") (pintype "passive"))
      (node (ref "U3") (pin "43") (pinfunction "VDDCORE_43") (pintype "power_in"))
    )
    (net (code "23") (name "Net-(U9-PROG)") (class "Default")
      (node (ref "R3") (pin "2") (pinfunction "2_2") (pintype "passive"))
      (node (ref "U9") (pin "8") (pinfunction "PROG_8") (pintype "bidirectional"))
    )
    (net (code "24") (name "Net-(U9-STAT)") (class "Default")
      (node (ref "DL2") (pin "C") (pinfunction "C_C") (pintype "passive"))
      (node (ref "U9") (pin "5") (pinfunction "STAT_5") (pintype "bidirectional"))
    )
    (net (code "25") (name "Net-(VUSB-TP)") (class "Default")
      (node (ref "D1") (pin "4") (pinfunction "4_4") (pintype "passive"))
      (node (ref "F2") (pin "2") (pinfunction "2_2") (pintype "passive"))
      (node (ref "J1") (pin "1") (pinfunction "1_1") (pintype "passive"))
      (node (ref "VUSB") (pin "PP") (pinfunction "TP_PP") (pintype "input"))
    )
    (net (code "26") (name "PA00_XIN32") (class "Default")
      (node (ref "C11") (pin "2") (pinfunction "2_2") (pintype "passive"))
      (node (ref "U3") (pin "1") (pinfunction "PA00/XIN32_1") (pintype "bidirectional"))
      (node (ref "Y1") (pin "2") (pinfunction "2_2") (pintype "passive"))
    )
    (net (code "27") (name "PA01_XOUT32") (class "Default")
      (node (ref "C9") (pin "2") (pinfunction "2_2") (pintype "passive"))
      (node (ref "U3") (pin "2") (pinfunction "PA01/XOUT32_2") (pintype "bidirectional"))
      (node (ref "Y1") (pin "1") (pinfunction "1_1") (pintype "passive"))
    )
    (net (code "28") (name "PA02_AIN0") (class "Default")
      (node (ref "J4") (pin "2") (pinfunction "2_2") (pintype "passive"))
      (node (ref "U3") (pin "3") (pinfunction "PA02_3") (pintype "bidirectional"))
    )
    (net (code "29") (name "PA03_VREFA") (class "Default")
      (node (ref "C12") (pin "1") (pinfunction "1_1") (pintype "passive"))
      (node (ref "C14") (pin "1") (pinfunction "1_1") (pintype "passive"))
      (node (ref "J4") (pin "1") (pinfunction "1_1") (pintype "passive"))
      (node (ref "U3") (pin "4") (pinfunction "PA03_4") (pintype "bidirectional"))
    )
    (net (code "30") (name "PA04_AIN4") (class "Default")
      (node (ref "J4") (pin "5") (pinfunction "5_5") (pintype "passive"))
      (node (ref "U3") (pin "9") (pinfunction "PA04_9") (pintype "bidirectional"))
    )
    (net (code "31") (name "PA05_AIN5") (class "Default")
      (node (ref "J4") (pin "6") (pinfunction "6_6") (pintype "passive"))
      (node (ref "U3") (pin "10") (pinfunction "PA05_10") (pintype "bidirectional"))
    )
    (net (code "32") (name "PA06_AIN6") (class "Default")
      (node (ref "J4") (pin "7") (pinfunction "7_7") (pintype "passive"))
      (node (ref "U3") (pin "11") (pinfunction "PA06_11") (pintype "bidirectional"))
    )
    (net (code "33") (name "PA07_AIN7") (class "Default")
      (node (ref "J4") (pin "8") (pinfunction "8_8") (pintype "passive"))
      (node (ref "U3") (pin "12") (pinfunction "PA07_12") (pintype "bidirectional"))
    )
    (net (code "34") (name "PA08_S0_I2C_SDA") (class "Default")
      (node (ref "ESDA") (pin "PP") (pinfunction "TP_PP") (pintype "input"))
      (node (ref "J5") (pin "6") (pinfunction "6_6") (pintype "passive"))
      (node (ref "J7") (pin "4") (pinfunction "4_4") (pintype "passive"))
      (node (ref "R23") (pin "1") (pinfunction "1_1") (pintype "passive"))
      (node (ref "U3") (pin "13") (pinfunction "PA08_13") (pintype "bidirectional"))
      (node (ref "U4") (pin "5") (pinfunction "SDA_5") (pintype "bidirectional"))
    )
    (net (code "35") (name "PA09_S0_I2C_SCL") (class "Default")
      (node (ref "ESCL") (pin "PP") (pinfunction "TP_PP") (pintype "input"))
      (node (ref "J5") (pin "7") (pinfunction "7_7") (pintype "passive"))
      (node (ref "J7") (pin "3") (pinfunction "3_3") (pintype "passive"))
      (node (ref "R22") (pin "1") (pinfunction "1_1") (pintype "passive"))
      (node (ref "U3") (pin "14") (pinfunction "PA09_14") (pintype "bidirectional"))
      (node (ref "U4") (pin "6") (pinfunction "SCL_6") (pintype "input"))
    )
    (net (code "36") (name "PA10_TCC0-W2") (class "Default")
      (node (ref "J4") (pin "11") (pinfunction "11_11") (pintype "passive"))
      (node (ref "U3") (pin "15") (pinfunction "PA10_15") (pintype "bidirectional"))
    )
    (net (code "37") (name "PA11_TCC0-W3") (class "Default")
      (node (ref "J4") (pin "12") (pinfunction "12_12") (pintype "passive"))
      (node (ref "U3") (pin "16") (pinfunction "PA11_16") (pintype "bidirectional"))
    )
    (net (code "38") (name "PA12_S2_MOSI") (class "Default")
      (node (ref "J3") (pin "3") (pinfunction "CMD_3") (pintype "bidirectional"))
      (node (ref "U3") (pin "21") (pinfunction "PA12_21") (pintype "bidirectional"))
    )
    (net (code "39") (name "PA13_S2_SCK") (class "Default")
      (node (ref "J3") (pin "5") (pinfunction "CLK_5") (pintype "bidirectional"))
      (node (ref "U3") (pin "22") (pinfunction "PA13_22") (pintype "bidirectional"))
    )
    (net (code "40") (name "PA14_S2_NSS") (class "Default")
      (node (ref "J3") (pin "2") (pinfunction "CD/DAT3_2") (pintype "bidirectional"))
      (node (ref "R17") (pin "1") (pinfunction "1_1") (pintype "passive"))
      (node (ref "U3") (pin "23") (pinfunction "PA14_23") (pintype "bidirectional"))
    )
    (net (code "41") (name "PA15_S2_MISO") (class "Default")
      (node (ref "J3") (pin "7") (pinfunction "DAT0_7") (pintype "bidirectional"))
      (node (ref "U3") (pin "24") (pinfunction "PA15_24") (pintype "bidirectional"))
    )
    (net (code "42") (name "PA16_S1_MOSI") (class "Default")
      (node (ref "J5") (pin "3") (pinfunction "3_3") (pintype "passive"))
      (node (ref "U3") (pin "25") (pinfunction "PA16_25") (pintype "bidirectional"))
    )
    (net (code "43") (name "PA17_S1_SCK") (class "Default")
      (node (ref "J5") (pin "4") (pinfunction "4_4") (pintype "passive"))
      (node (ref "U3") (pin "26") (pinfunction "PA17_26") (pintype "bidirectional"))
    )
    (net (code "44") (name "PA18_USB_ID") (class "Default")
      (node (ref "D3") (pin "A") (pinfunction "A_A") (pintype "passive"))
      (node (ref "U3") (pin "27") (pinfunction "PA18_27") (pintype "bidirectional"))
    )
    (net (code "45") (name "PA19_S1_MISO") (class "Default")
      (node (ref "J5") (pin "5") (pinfunction "5_5") (pintype "passive"))
      (node (ref "U3") (pin "28") (pinfunction "PA19_28") (pintype "bidirectional"))
    )
    (net (code "46") (name "PA20_TCC0-W6") (class "Default")
      (node (ref "J5") (pin "1") (pinfunction "1_1") (pintype "passive"))
      (node (ref "U3") (pin "29") (pinfunction "PA20_29") (pintype "bidirectional"))
    )
    (net (code "47") (name "PA21_TCC0-W7") (class "Default")
      (node (ref "EWK") (pin "PP") (pinfunction "TP_PP") (pintype "input"))
      (node (ref "J5") (pin "2") (pinfunction "2_2") (pintype "passive"))
      (node (ref "J7") (pin "2") (pinfunction "2_2") (pintype "passive"))
      (node (ref "U3") (pin "30") (pinfunction "PA21_30") (pintype "bidirectional"))
    )
    (net (code "48") (name "PA22_TC4-W0") (class "Default")
      (node (ref "J4") (pin "9") (pinfunction "9_9") (pintype "passive"))
      (node (ref "U3") (pin "31") (pinfunction "PA22_31") (pintype "bidirectional"))
    )
    (net (code "49") (name "PA23_TC4-W1") (class "Default")
      (node (ref "J4") (pin "10") (pinfunction "10_10") (pintype "passive"))
      (node (ref "U3") (pin "32") (pinfunction "PA23_32") (pintype "bidirectional"))
    )
    (net (code "50") (name "PA27_CD") (class "Default")
      (node (ref "J3") (pin "CD1") (pinfunction "CD1_CD1") (pintype "bidirectional"))
      (node (ref "U3") (pin "39") (pinfunction "PA27_39") (pintype "bidirectional"))
    )
    (net (code "51") (name "PA30_SWCLK") (class "Default")
      (node (ref "J8") (pin "4") (pinfunction "4_4") (pintype "passive"))
      (node (ref "R7") (pin "1") (pinfunction "1_1") (pintype "passive"))
      (node (ref "U3") (pin "45") (pinfunction "PA30/SWCLK_45") (pintype "bidirectional"))
    )
    (net (code "52") (name "PA31_SWDIO") (class "Default")
      (node (ref "J8") (pin "2") (pinfunction "2_2") (pintype "passive"))
      (node (ref "U3") (pin "46") (pinfunction "PA31/SWDIO_46") (pintype "bidirectional"))
    )
    (net (code "53") (name "PB02_AIN10") (class "Default")
      (node (ref "J4") (pin "3") (pinfunction "3_3") (pintype "passive"))
      (node (ref "U3") (pin "47") (pinfunction "PB02_47") (pintype "bidirectional"))
    )
    (net (code "54") (name "PB03_AIN11") (class "Default")
      (node (ref "J4") (pin "4") (pinfunction "4_4") (pintype "passive"))
      (node (ref "U3") (pin "48") (pinfunction "PB03_48") (pintype "bidirectional"))
    )
    (net (code "55") (name "PB08_LED") (class "Default")
      (node (ref "R18") (pin "1") (pinfunction "1_1") (pintype "passive"))
      (node (ref "U3") (pin "7") (pinfunction "PB08_7") (pintype "bidirectional"))
    )
    (net (code "56") (name "PB10_TCC0-W4") (class "Default")
      (node (ref "J4") (pin "13") (pinfunction "13_13") (pintype "passive"))
      (node (ref "U3") (pin "19") (pinfunction "PB10_19") (pintype "bidirectional"))
    )
    (net (code "57") (name "PB11_TCC0-W5") (class "Default")
      (node (ref "J4") (pin "14") (pinfunction "14_14") (pintype "passive"))
      (node (ref "U3") (pin "20") (pinfunction "PB11_20") (pintype "bidirectional"))
    )
    (net (code "58") (name "PB22_S5_TX") (class "Default")
      (node (ref "J5") (pin "9") (pinfunction "9_9") (pintype "passive"))
      (node (ref "U3") (pin "37") (pinfunction "PB22_37") (pintype "bidirectional"))
    )
    (net (code "59") (name "PB23_S5_RX") (class "Default")
      (node (ref "J5") (pin "8") (pinfunction "8_8") (pintype "passive"))
      (node (ref "U3") (pin "38") (pinfunction "PB23_38") (pintype "bidirectional"))
    )
    (net (code "60") (name "RESET#") (class "Default")
      (node (ref "J5") (pin "10") (pinfunction "10_10") (pintype "passive"))
      (node (ref "R20") (pin "2") (pinfunction "2_2") (pintype "passive"))
    )
    (net (code "61") (name "RESETN") (class "Default")
      (node (ref "C7") (pin "1") (pinfunction "1_1") (pintype "passive"))
      (node (ref "R13") (pin "2") (pinfunction "2_2") (pintype "passive"))
      (node (ref "R15") (pin "2") (pinfunction "2_2") (pintype "passive"))
      (node (ref "R16") (pin "1") (pinfunction "1_1") (pintype "passive"))
      (node (ref "R20") (pin "1") (pinfunction "1_1") (pintype "passive"))
      (node (ref "U3") (pin "40") (pinfunction "RESETN_40") (pintype "bidirectional"))
    )
    (net (code "62") (name "USB_ID") (class "Default")
      (node (ref "D2") (pin "C") (pinfunction "C_C") (pintype "passive"))
      (node (ref "D3") (pin "C") (pinfunction "C_C") (pintype "passive"))
      (node (ref "J1") (pin "4") (pinfunction "4_4") (pintype "passive"))
      (node (ref "USB_ID") (pin "PP") (pinfunction "TP_PP") (pintype "input"))
    )
    (net (code "63") (name "USB_N") (class "Default")
      (node (ref "D-") (pin "PP") (pinfunction "TP_PP") (pintype "input"))
      (node (ref "D1") (pin "3") (pinfunction "3_3") (pintype "passive"))
      (node (ref "J1") (pin "2") (pinfunction "2_2") (pintype "passive"))
      (node (ref "U3") (pin "33") (pinfunction "PA24/USB_DM_33") (pintype "bidirectional"))
    )
    (net (code "64") (name "USB_P") (class "Default")
      (node (ref "D+") (pin "PP") (pinfunction "TP_PP") (pintype "input"))
      (node (ref "D1") (pin "2") (pinfunction "2_2") (pintype "passive"))
      (node (ref "J1") (pin "3") (pinfunction "3_3") (pintype "passive"))
      (node (ref "U3") (pin "34") (pinfunction "PA25/USB_DP_34") (pintype "bidirectional"))
    )
    (net (code "65") (name "VBATT") (class "Default")
      (node (ref "BATT+") (pin "PP") (pinfunction "TP_PP") (pintype "input"))
      (node (ref "C3") (pin "1") (pinfunction "1_1") (pintype "passive"))
      (node (ref "D4") (pin "C") (pinfunction "C_C") (pintype "passive"))
      (node (ref "F1") (pin "2") (pinfunction "2_2") (pintype "passive"))
      (node (ref "Q3") (pin "D") (pinfunction "D_D") (pintype "passive"))
      (node (ref "Q3") (pin "D2") (pinfunction "D_D2") (pintype "passive"))
      (node (ref "R19") (pin "2") (pinfunction "2_2") (pintype "passive"))
      (node (ref "U9") (pin "3") (pinfunction "VBAT_3") (pintype "bidirectional"))
      (node (ref "U9") (pin "4") (pinfunction "VBAT_4") (pintype "bidirectional"))
    )
    (net (code "66") (name "VIN") (class "Default")
      (node (ref "J5") (pin "13") (pinfunction "13_13") (pintype "passive"))
      (node (ref "Q5") (pin "D1") (pinfunction "D_D1") (pintype "passive"))
      (node (ref "Q5") (pin "D1'") (pinfunction "D_D1'") (pintype "passive"))
      (node (ref "R11") (pin "2") (pinfunction "2_2") (pintype "passive"))
    )
    (net (code "67") (name "VUSB") (class "Default")
      (node (ref "C5") (pin "1") (pinfunction "1_1") (pintype "passive"))
      (node (ref "L2") (pin "2") (pinfunction "2_2") (pintype "passive"))
      (node (ref "Q2") (pin "D1") (pinfunction "D_D1") (pintype "passive"))
      (node (ref "Q2") (pin "D1'") (pinfunction "D_D1'") (pintype "passive"))
      (node (ref "R6") (pin "2") (pinfunction "2_2") (pintype "passive"))
    )
    (net (code "68") (name "unconnected-(J3-DAT1-Pad8)") (class "Default")
      (node (ref "J3") (pin "8") (pinfunction "DAT1_8") (pintype "bidirectional"))
    )
    (net (code "69") (name "unconnected-(J3-DATA2-Pad1)") (class "Default")
      (node (ref "J3") (pin "1") (pinfunction "DATA2_1") (pintype "bidirectional"))
    )
    (net (code "70") (name "unconnected-(J8-Pad6)") (class "Default")
      (node (ref "J8") (pin "6") (pinfunction "6_6") (pintype "passive"))
    )
    (net (code "71") (name "unconnected-(U4B-EP-Pad9)") (class "Default")
      (node (ref "U4") (pin "9") (pinfunction "EP_9") (pintype "passive"))
    )
    (net (code "72") (name "unconnected-(U4B-NC-Pad1)") (class "Default")
      (node (ref "U4") (pin "1") (pinfunction "NC_1") (pintype "bidirectional"))
    )
    (net (code "73") (name "unconnected-(U4B-NC-Pad2)") (class "Default")
      (node (ref "U4") (pin "2") (pinfunction "NC_2") (pintype "bidirectional"))
    )
    (net (code "74") (name "unconnected-(U4B-NC-Pad3)") (class "Default")
      (node (ref "U4") (pin "3") (pinfunction "NC_3") (pintype "bidirectional"))
    )
    (net (code "75") (name "unconnected-(U4B-NC-Pad7)") (class "Default")
      (node (ref "U4") (pin "7") (pinfunction "NC_7") (pintype "bidirectional"))
    )
  )
)
